# Controller1.net
KiCad netlist of a schematic drawn in EAGLE
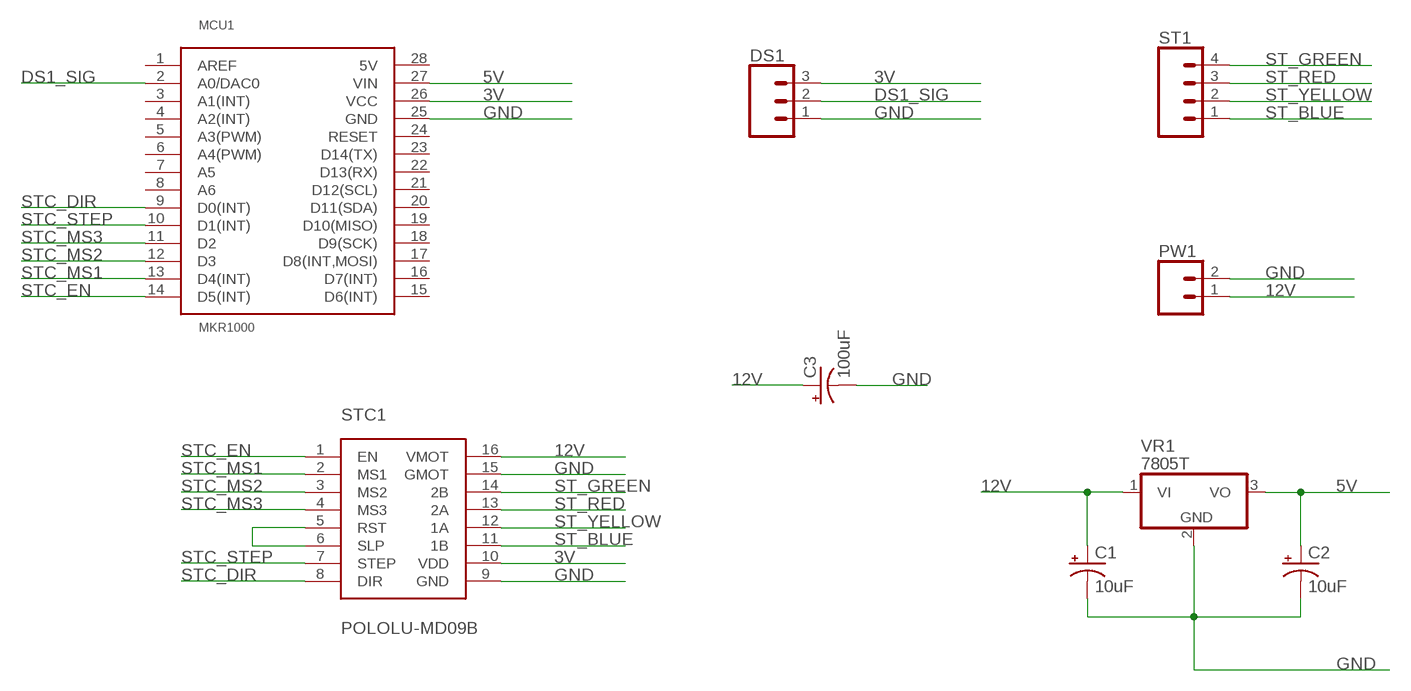
[diagram p0: schematic, sheet 1]

(export (version "E")
  (design (tool "Eeschema 10.0.6"))
  (components
    (comp (ref "C1")
      (value "10uF")
      (footprint "eagle-import:E2-5")
      (libsource (lib "eagle-import") (part "CPOL-USE2-5"))
    )
    (comp (ref "C2")
      (value "10uF")
      (footprint "eagle-import:E2-5")
      (libsource (lib "eagle-import") (part "CPOL-USE2-5"))
    )
    (comp (ref "C3")
      (value "100uF")
      (footprint "eagle-import:E2-5")
      (libsource (lib "eagle-import") (part "CPOL-USE2-5"))
    )
    (comp (ref "DS1")
      (value "CONN_03LONGPADS")
      (footprint "eagle-import:1X03_LONGPADS")
      (libsource (lib "eagle-import") (part "CONN_03LONGPADS"))
    )
    (comp (ref "MCU1")
      (value "MKR1000")
      (footprint "eagle-import:MKR1000-SOCKET")
      (libsource (lib "eagle-import") (part "MKR1000"))
    )
    (comp (ref "PW1")
      (value "CONN_025MM")
      (footprint "eagle-import:SCREWTERMINAL-5MM-2")
      (libsource (lib "eagle-import") (part "CONN_025MM"))
    )
    (comp (ref "ST1")
      (value "CONN_04LONGPADS")
      (footprint "eagle-import:1X04_LONGPADS")
      (libsource (lib "eagle-import") (part "CONN_04LONGPADS"))
    )
    (comp (ref "STC1")
      (value "POLOLU-MD09B")
      (footprint "eagle-import:POLOLU-MD09B")
      (libsource (lib "eagle-import") (part "POLOLU-MD09B"))
    )
    (comp (ref "VR1")
      (value "7805T")
      (footprint "eagle-import:TO220H")
      (libsource (lib "eagle-import") (part "78T05"))
    )
  )
  (nets
    (net (code "1") (name "/3V") (class "Default")
      (node (ref "DS1") (pin "3") (pinfunction "3_3") (pintype "passive"))
      (node (ref "MCU1") (pin "26") (pinfunction "VCC_26") (pintype "bidirectional"))
      (node (ref "STC1") (pin "10") (pinfunction "VDD_10") (pintype "bidirectional"))
    )
    (net (code "2") (name "/5V") (class "Default")
      (node (ref "C2") (pin "+") (pinfunction "+_+") (pintype "passive"))
      (node (ref "MCU1") (pin "27") (pinfunction "VIN_27") (pintype "bidirectional"))
      (node (ref "VR1") (pin "3") (pinfunction "VO_3") (pintype "passive"))
    )
    (net (code "3") (name "/12V") (class "Default")
      (node (ref "C1") (pin "+") (pinfunction "+_+") (pintype "passive"))
      (node (ref "C3") (pin "+") (pinfunction "+_+") (pintype "passive"))
      (node (ref "PW1") (pin "1") (pinfunction "1_1") (pintype "passive"))
      (node (ref "STC1") (pin "16") (pinfunction "VMOT_16") (pintype "bidirectional"))
      (node (ref "VR1") (pin "1") (pinfunction "VI_1") (pintype "input"))
    )
    (net (code "4") (name "/DS1_SIG") (class "Default")
      (node (ref "DS1") (pin "2") (pinfunction "2_2") (pintype "passive"))
      (node (ref "MCU1") (pin "2") (pinfunction "A0/DAC0_2") (pintype "bidirectional"))
    )
    (net (code "5") (name "/GND") (class "Default")
      (node (ref "C1") (pin "-") (pinfunction "-_-") (pintype "passive"))
      (node (ref "C2") (pin "-") (pinfunction "-_-") (pintype "passive"))
      (node (ref "C3") (pin "-") (pinfunction "-_-") (pintype "passive"))
      (node (ref "DS1") (pin "1") (pinfunction "1_1") (pintype "passive"))
      (node (ref "MCU1") (pin "25") (pinfunction "GND_25") (pintype "bidirectional"))
      (node (ref "PW1") (pin "2") (pinfunction "2_2") (pintype "passive"))
      (node (ref "STC1") (pin "15") (pinfunction "GMOT_15") (pintype "bidirectional"))
      (node (ref "STC1") (pin "9") (pinfunction "GND_9") (pintype "bidirectional"))
      (node (ref "VR1") (pin "2") (pinfunction "GND_2") (pintype "passive"))
    )
    (net (code "6") (name "/STC_DIR") (class "Default")
      (node (ref "MCU1") (pin "9") (pinfunction "D0(INT)_9") (pintype "bidirectional"))
      (node (ref "STC1") (pin "8") (pinfunction "DIR_8") (pintype "bidirectional"))
    )
    (net (code "7") (name "/STC_EN") (class "Default")
      (node (ref "MCU1") (pin "14") (pinfunction "D5(INT)_14") (pintype "bidirectional"))
      (node (ref "STC1") (pin "1") (pinfunction "EN_1") (pintype "bidirectional"))
    )
    (net (code "8") (name "/STC_MS1") (class "Default")
      (node (ref "MCU1") (pin "13") (pinfunction "D4(INT)_13") (pintype "bidirectional"))
      (node (ref "STC1") (pin "2") (pinfunction "MS1_2") (pintype "bidirectional"))
    )
    (net (code "9") (name "/STC_MS2") (class "Default")
      (node (ref "MCU1") (pin "12") (pinfunction "D3_12") (pintype "bidirectional"))
      (node (ref "STC1") (pin "3") (pinfunction "MS2_3") (pintype "bidirectional"))
    )
    (net (code "10") (name "/STC_MS3") (class "Default")
      (node (ref "MCU1") (pin "11") (pinfunction "D2_11") (pintype "bidirectional"))
      (node (ref "STC1") (pin "4") (pinfunction "MS3_4") (pintype "bidirectional"))
    )
    (net (code "11") (name "/STC_STEP") (class "Default")
      (node (ref "MCU1") (pin "10") (pinfunction "D1(INT)_10") (pintype "bidirectional"))
      (node (ref "STC1") (pin "7") (pinfunction "STEP_7") (pintype "bidirectional"))
    )
    (net (code "12") (name "/ST_BLUE") (class "Default")
      (node (ref "ST1") (pin "1") (pinfunction "1_1") (pintype "passive"))
      (node (ref "STC1") (pin "11") (pinfunction "1B_11") (pintype "bidirectional"))
    )
    (net (code "13") (name "/ST_GREEN") (class "Default")
      (node (ref "ST1") (pin "4") (pinfunction "4_4") (pintype "passive"))
      (node (ref "STC1") (pin "14") (pinfunction "2B_14") (pintype "bidirectional"))
    )
    (net (code "14") (name "/ST_RED") (class "Default")
      (node (ref "ST1") (pin "3") (pinfunction "3_3") (pintype "passive"))
      (node (ref "STC1") (pin "13") (pinfunction "2A_13") (pintype "bidirectional"))
    )
    (net (code "15") (name "/ST_YELLOW") (class "Default")
      (node (ref "ST1") (pin "2") (pinfunction "2_2") (pintype "passive"))
      (node (ref "STC1") (pin "12") (pinfunction "1A_12") (pintype "bidirectional"))
    )
    (net (code "16") (name "Net-(STC1-RST)") (class "Default")
      (node (ref "STC1") (pin "5") (pinfunction "RST_5") (pintype "bidirectional"))
      (node (ref "STC1") (pin "6") (pinfunction "SLP_6") (pintype "bidirectional"))
    )
    (net (code "17") (name "unconnected-(MCU1-5V-Pad28)") (class "Default")
      (node (ref "MCU1") (pin "28") (pinfunction "5V_28") (pintype "bidirectional"))
    )
    (net (code "18") (name "unconnected-(MCU1-A1(INT)-Pad3)") (class "Default")
      (node (ref "MCU1") (pin "3") (pinfunction "A1(INT)_3") (pintype "bidirectional"))
    )
    (net (code "19") (name "unconnected-(MCU1-A2(INT)-Pad4)") (class "Default")
      (node (ref "MCU1") (pin "4") (pinfunction "A2(INT)_4") (pintype "bidirectional"))
    )
    (net (code "20") (name "unconnected-(MCU1-A3(PWM)-Pad5)") (class "Default")
      (node (ref "MCU1") (pin "5") (pinfunction "A3(PWM)_5") (pintype "bidirectional"))
    )
    (net (code "21") (name "unconnected-(MCU1-A4(PWM)-Pad6)") (class "Default")
      (node (ref "MCU1") (pin "6") (pinfunction "A4(PWM)_6") (pintype "bidirectional"))
    )
    (net (code "22") (name "unconnected-(MCU1-A5-Pad7)") (class "Default")
      (node (ref "MCU1") (pin "7") (pinfunction "A5_7") (pintype "bidirectional"))
    )
    (net (code "23") (name "unconnected-(MCU1-A6-Pad8)") (class "Default")
      (node (ref "MCU1") (pin "8") (pinfunction "A6_8") (pintype "bidirectional"))
    )
    (net (code "24") (name "unconnected-(MCU1-AREF-Pad1)") (class "Default")
      (node (ref "MCU1") (pin "1") (pinfunction "AREF_1") (pintype "bidirectional"))
    )
    (net (code "25") (name "unconnected-(MCU1-D6(INT)-Pad15)") (class "Default")
      (node (ref "MCU1") (pin "15") (pinfunction "D6(INT)_15") (pintype "bidirectional"))
    )
    (net (code "26") (name "unconnected-(MCU1-D7(INT)-Pad16)") (class "Default")
      (node (ref "MCU1") (pin "16") (pinfunction "D7(INT)_16") (pintype "bidirectional"))
    )
    (net (code "27") (name "unconnected-(MCU1-D8(INT,MOSI)-Pad17)") (class "Default")
      (node (ref "MCU1") (pin "17") (pinfunction "D8(INT,MOSI)_17") (pintype "bidirectional"))
    )
    (net (code "28") (name "unconnected-(MCU1-D9(SCK)-Pad18)") (class "Default")
      (node (ref "MCU1") (pin "18") (pinfunction "D9(SCK)_18") (pintype "bidirectional"))
    )
    (net (code "29") (name "unconnected-(MCU1-D10(MISO)-Pad19)") (class "Default")
      (node (ref "MCU1") (pin "19") (pinfunction "D10(MISO)_19") (pintype "bidirectional"))
    )
    (net (code "30") (name "unconnected-(MCU1-D11(SDA)-Pad20)") (class "Default")
      (node (ref "MCU1") (pin "20") (pinfunction "D11(SDA)_20") (pintype "bidirectional"))
    )
    (net (code "31") (name "unconnected-(MCU1-D12(SCL)-Pad21)") (class "Default")
      (node (ref "MCU1") (pin "21") (pinfunction "D12(SCL)_21") (pintype "bidirectional"))
    )
    (net (code "32") (name "unconnected-(MCU1-D13(RX)-Pad22)") (class "Default")
      (node (ref "MCU1") (pin "22") (pinfunction "D13(RX)_22") (pintype "bidirectional"))
    )
    (net (code "33") (name "unconnected-(MCU1-D14(TX)-Pad23)") (class "Default")
      (node (ref "MCU1") (pin "23") (pinfunction "D14(TX)_23") (pintype "bidirectional"))
    )
    (net (code "34") (name "unconnected-(MCU1-RESET-Pad24)") (class "Default")
      (node (ref "MCU1") (pin "24") (pinfunction "RESET_24") (pintype "bidirectional"))
    )
  )
)
